# rPi.net
KiCad netlist of a schematic drawn in Altium Designer
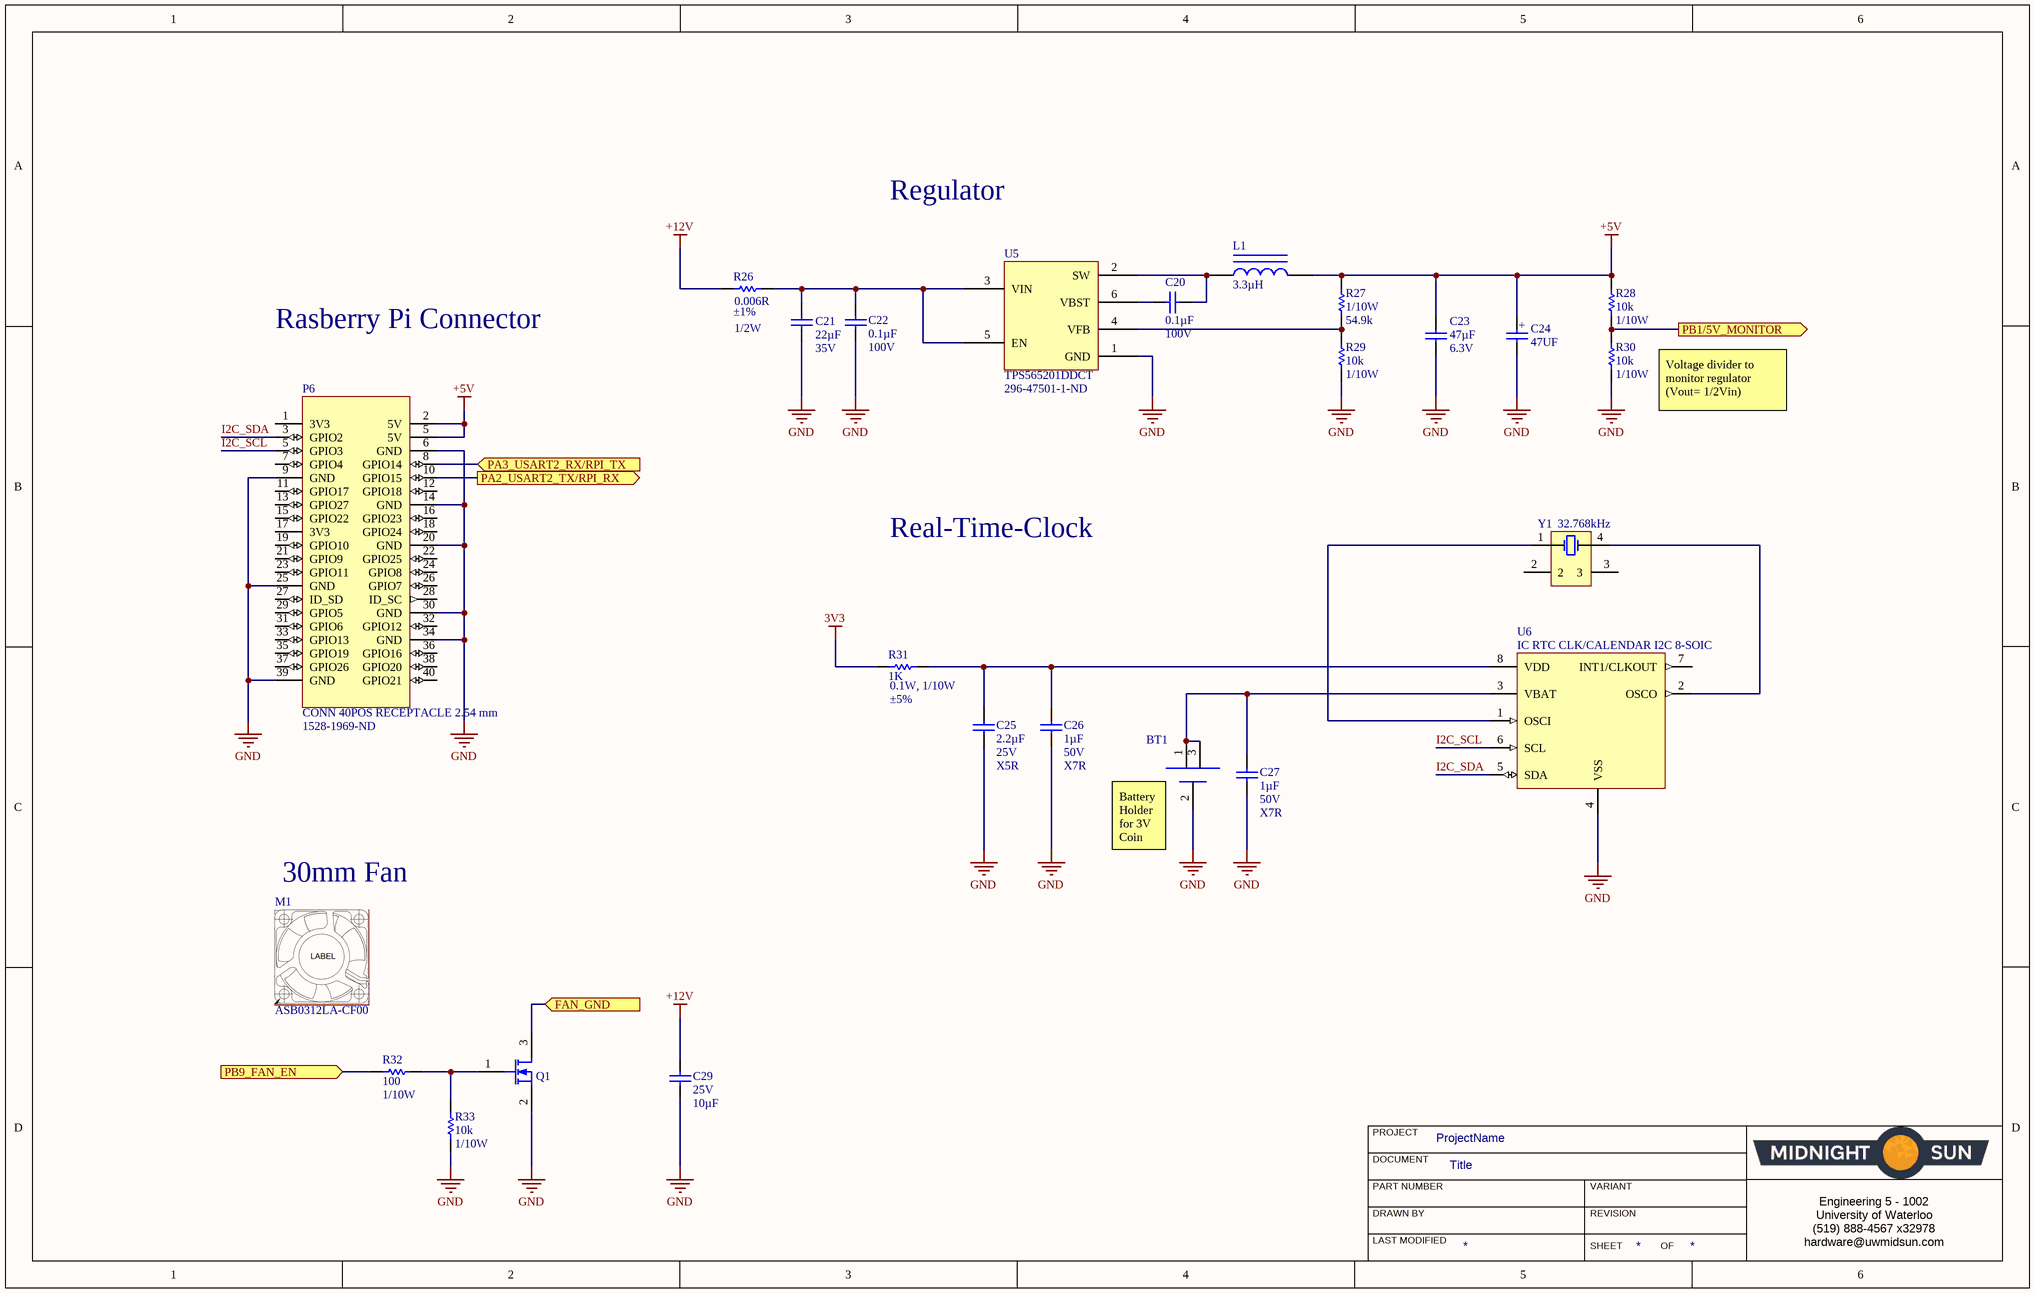
[diagram p0: rPi.SchDoc]

(export (version "E")
  (design (tool "Eeschema 10.0.6"))
  (components
    (comp (ref "BT1")
      (value "HOLDER BATTERY COIN 12MM DIA")
      (footprint "HOLDER COIN CELL 1220 3V")
      (description "Coin cell holder smd")
      (fields
        (field (name "MANUFACTURER") "Keystone Electronics")
        (field (name "MANUFACTURER PART NUMBER") "3000")
      )
      (libsource (lib "Schematic Diagrams") (part "HOLDER BATTERY COIN 12MM DIA"))
    )
    (comp (ref "C20")
      (value "CAP CER 0.1UF 100V 10% X7R 0805")
      (footprint "CAP, 0805")
      (description "0.1µF ±10% 100V Ceramic Capacitor X7R 0805 (2012 Metric)")
      (fields
        (field (name "TOLERANCE") "±10%")
        (field (name "CAPACITANCE") "0.1µF")
        (field (name "VOLTAGE") "100V")
      )
      (libsource (lib "Schematic Diagrams") (part "CAP CER 0.1UF 100V 10% X7R 0805"))
    )
    (comp (ref "C21")
      (value "CAP CER 22UF 35V X5R 0805")
      (footprint "CAP, 0805")
      (description "22µF ±20% 35V Ceramic Capacitor X5R 0805 (2012 Metric)")
      (fields
        (field (name "MANUFACTURER") "TDK")
        (field (name "MANUFACTURER PART NUMBER") "C2012X5R1V226M125AC")
      )
      (libsource (lib "Schematic Diagrams") (part "CAP CER 22UF 35V X5R 0805"))
    )
    (comp (ref "C22")
      (value "CAP CER 0.1UF 100V 10% X7R 0805")
      (footprint "CAP, 0805")
      (description "0.1µF ±10% 100V Ceramic Capacitor X7R 0805 (2012 Metric)")
      (fields
        (field (name "TOLERANCE") "±10%")
        (field (name "CAPACITANCE") "0.1µF")
        (field (name "VOLTAGE") "100V")
      )
      (libsource (lib "Schematic Diagrams") (part "CAP CER 0.1UF 100V 10% X7R 0805"))
    )
    (comp (ref "C23")
      (value "CAP CER 47UF 6.3V X7R 1210")
      (footprint "1210")
      (description "47µF ±10% 6.3V Ceramic Capacitor X7R 1210 (3225 Metric)")
      (fields
        (field (name "MANUFACTURER") "Murata")
        (field (name "MANUFACTURER PART NUMBER") "GCJ32ER70J476KE01L")
      )
      (libsource (lib "Schematic Diagrams") (part "CAP CER 47UF 6.3V X7R 1210"))
    )
    (comp (ref "C24")
      (value "47UF")
      (footprint "CAP ALUM 6.3MM RADIAL SMD")
      (description "47µF 35V Aluminum Electrolytic Capacitors Radial, Can - SMD 1000 Hrs @ 85°C")
      (fields
        (field (name "MANUFACTURER") "Panasonic")
        (field (name "MANUFACTURER PART NUMBER") "EEE-1VA470WP")
      )
      (libsource (lib "Schematic Diagrams") (part "CAP ALUM 47UF 20% 35V SMD"))
    )
    (comp (ref "C25")
      (value "CAP CER 2.2UF 25V 10% X5R 0603")
      (footprint "CAP, 0603")
      (description "2.2µF ±10% 25V Ceramic Capacitor X5R 0603 (1608 Metric)")
      (fields
        (field (name "TOLERANCE") "±10%")
        (field (name "CAPACITANCE") "2.2µF")
        (field (name "VOLTAGE") "25V")
        (field (name "TEMPERATURE COEFFICIENT") "X5R")
      )
      (libsource (lib "Schematic Diagrams") (part "CAP CER 2.2UF 25V 10% X5R 0603"))
    )
    (comp (ref "C26")
      (value "CAP CER 1UF 50V 10% X7R 0603")
      (footprint "CAP, 0603")
      (description "1µF ±10% 50V Ceramic Capacitor X7R 0603 (1608 Metric)")
      (fields
        (field (name "TOLERANCE") "±10%")
        (field (name "CAPACITANCE") "1µF")
        (field (name "VOLTAGE") "50V")
        (field (name "TEMPERATURE COEFFICIENT") "X7R")
      )
      (libsource (lib "Schematic Diagrams") (part "CAP CER 1UF 50V 10% X7R 0603"))
    )
    (comp (ref "C27")
      (value "CAP CER 1UF 50V 10% X7R 0603")
      (footprint "CAP, 0603")
      (description "1µF ±10% 50V Ceramic Capacitor X7R 0603 (1608 Metric)")
      (fields
        (field (name "TOLERANCE") "±10%")
        (field (name "CAPACITANCE") "1µF")
        (field (name "VOLTAGE") "50V")
        (field (name "TEMPERATURE COEFFICIENT") "X7R")
      )
      (libsource (lib "Schematic Diagrams") (part "CAP CER 1UF 50V 10% X7R 0603"))
    )
    (comp (ref "C29")
      (value "CAP CER 10uF 25V 10% X5R 0805")
      (footprint "CAP, 0805")
      (description "10µF ±10% 25V Ceramic Capacitor X5R 0805 (2012 Metric)")
      (fields
        (field (name "MANUFACTURER") "Murata Electronics North America")
        (field (name "MANUFACTURER PART NUMBER") "GRM21BR61E106KA73L")
        (field (name "VOLTAGE - RATED") "25V")
        (field (name "CAPACITANCE") "10µF")
      )
      (libsource (lib "altium-import") (part "root_0_CAP CER 10uF 25V 10% X5R 0805_"))
    )
    (comp (ref "L1")
      (value "IND 3.3uH 5.2A 20MOHM SMD")
      (footprint "IND 3.3UH 5.2A 20 MOHM SMD VLP8040")
      (description "3.3µH Shielded Wirewound Inductor 5.2A 20 mOhm Max Nonstandard")
      (fields
        (field (name "MANUFACTURER") "TDK Corporation")
        (field (name "MANUFACTURER PART NUMBER") "VLS201612CX-3R3M")
        (field (name "INDUCTANCE") "3.3µH")
      )
      (libsource (lib "Schematic Diagrams") (part "IND 3.3uH 5.2A 20MOHM SMD"))
    )
    (comp (ref "M1")
      (value "FAN AXIAL 30x10MM 12VDC")
      (footprint "FAN AXIAL 30x10MM 12VDC")
      (description "FAN AXIAL 30X10MM 12VDC WIRE")
      (fields
        (field (name "MANUFACTURER") "Delta Design")
        (field (name "MANUFACTURER PART NUMBER") "ASB0312LA-CF00")
      )
      (libsource (lib "altium-import") (part "root_0_FAN AXIAL 30x10MM 12VDC_"))
    )
    (comp (ref "P6")
      (value "CONN 40POS RECEPTACLE 2.54 mm")
      (footprint "CONN 40POS RECEPTACLE 2.54 MM")
      (description "GPIO HEADER FOR RASPBERRYPI A+/B")
      (fields
        (field (name "MANUFACTURER") "Adafruit Industries")
        (field (name "MANUFACTURER PART NUMBER") "1992")
        (field (name "SUPPLIER PART NUMBER 1") "1528-1969-ND")
      )
      (libsource (lib "Schematic Diagrams") (part "CONN 40POS RECEPTACLE 2.54 mm"))
    )
    (comp (ref "Q1")
      (value "MOSFET N-CH 30V 6.2A 0.9W SOT-23")
      (footprint "MOSFET N-CH 30V 6.2A 0.9W SOT-23")
      (description "N-Channel 30V 6.2A (Ta) 900mW (Ta) Surface Mount SOT-23")
      (fields (field (name "MANUFACTURER") "Diodes") (field (name "MANUFACTURER PART NUMBER") "DMN3023L-7"))
      (libsource (lib "altium-import") (part "root_0_MOSFET N-CH 30V 6.2A 0.9W SOT-23_"))
    )
    (comp (ref "R26")
      (value "RES 0.006 OHM 1% 1/2W 1206")
      (footprint "RES 1206")
      (fields
        (field (name "TOLERANCE") "±1%")
        (field (name "MANUFACTURER") "Panasonic Electronic Components")
        (field (name "MANUFACTURER PART NUMBER") "ERJ-MP2KF6M0U")
        (field (name "RESISTANCE (OHMS)") "0.006R")
        (field (name "POWER (WATTS)") "1/2W")
      )
      (libsource (lib "Schematic Diagrams") (part "RES 0.006 OHM 1% 1/2W 1206"))
    )
    (comp (ref "R27")
      (value "RES 54.9K OHM 1% 1/10W 0603")
      (footprint "RES, 0603")
      (description "54.9k Ohm ±1% 0.1W, 1/10W Chip Resistor 0603 (1608 Metric) Automotive AEC-Q200 Thick Film")
      (fields
        (field (name "MANUFACTURER") "Panasonic Electronic Components")
        (field (name "MANUFACTURER PART NUMBER") "ERJ-3EKF5492V")
        (field (name "POWER (WATTS)") "1/10W")
        (field (name "RESISTANCE (OHMS)") "54.9k")
      )
      (libsource (lib "Schematic Diagrams") (part "RES 54.9K OHM 1% 1/10W 0603"))
    )
    (comp (ref "R28")
      (value "RES 10K OHM 1% 1/10W 0603")
      (footprint "RES, 0603")
      (description "RES SMD 10K OHM 1% 1/10W 0603")
      (fields
        (field (name "TOLERANCE") "±1%")
        (field (name "RESISTANCE") "10k")
        (field (name "POWER") "1/10W")
      )
      (libsource (lib "Schematic Diagrams") (part "RES 10K OHM 1% 1/10W 0603"))
    )
    (comp (ref "R29")
      (value "RES 10K OHM 1% 1/10W 0603")
      (footprint "RES, 0603")
      (description "RES SMD 10K OHM 1% 1/10W 0603")
      (fields
        (field (name "TOLERANCE") "±1%")
        (field (name "RESISTANCE") "10k")
        (field (name "POWER") "1/10W")
      )
      (libsource (lib "Schematic Diagrams") (part "RES 10K OHM 1% 1/10W 0603"))
    )
    (comp (ref "R30")
      (value "RES 10K OHM 1% 1/10W 0603")
      (footprint "RES, 0603")
      (description "RES SMD 10K OHM 1% 1/10W 0603")
      (fields
        (field (name "TOLERANCE") "±1%")
        (field (name "RESISTANCE") "10k")
        (field (name "POWER") "1/10W")
      )
      (libsource (lib "Schematic Diagrams") (part "RES 10K OHM 1% 1/10W 0603"))
    )
    (comp (ref "R31")
      (value "1K")
      (footprint "RES, 0603")
      (description "1k Ohm ±5% 0.1W, 1/10W Chip Resistor 0603 (1608 Metric)")
      (fields
        (field (name "MANUFACTURER") "Yageo")
        (field (name "MANUFACTURER PART NUMBER") "RC0603JR-071KL")
        (field (name "TOLERANCE") "±5%")
        (field (name "POWER (WATTS)") "0.1W, 1/10W")
      )
      (libsource (lib "Schematic Diagrams") (part "RES 1K OHM 5% 1/10W 0603"))
    )
    (comp (ref "R32")
      (value "RES 100 OHM 1% 1/10W 0603")
      (footprint "RES, 0603")
      (description "100 Ohm ±1% 0.1W, 1/10W Chip Resistor 0603 (1608 Metric) Moisture Resistant Thick Film")
      (fields
        (field (name "TOLERANCE") "±1%")
        (field (name "RESISTANCE") "100")
        (field (name "POWER") "1/10W")
      )
      (libsource (lib "altium-import") (part "root_1_RES 100 OHM 1% 1/10W 0603_"))
    )
    (comp (ref "R33")
      (value "RES 10K OHM 1% 1/10W 0603")
      (footprint "RES, 0603")
      (description "RES SMD 10K OHM 1% 1/10W 0603")
      (fields
        (field (name "TOLERANCE") "±1%")
        (field (name "RESISTANCE") "10k")
        (field (name "POWER") "1/10W")
      )
      (libsource (lib "altium-import") (part "root_0_RES 10K OHM 1% 1/10W 0603_"))
    )
    (comp (ref "U5")
      (value "IC REG BUCK 4.5V TO 17V, 5A, SYNCHRONOUS STE")
      (footprint "IC REG BUCK 4.5V TO 17V, 5A")
      (description "Buck Switching Regulator IC Positive Adjustable 0.6V 1 Output 5A SOT-23-6 Thin, TSOT-23-6")
      (fields
        (field (name "MANUFACTURER") "Texas Instruments")
        (field (name "MANUFACTURER PART NUMBER") "TPS565201DDCT")
        (field (name "SUPPLIER PART NUMBER 1") "296-47501-1-ND")
      )
      (libsource (lib "Schematic Diagrams") (part "IC REG BUCK 4.5V TO 17V, 5A, SYNCHRONOUS STE"))
    )
    (comp (ref "U6")
      (value "IC RTC CLK/CALENDAR I2C 8-SOIC")
      (footprint "SOIC8")
      (description "Real Time Clock (RTC) IC Clock/Calendar I²C, 2-Wire Serial 8-SOIC (0.154\", 3.90mm Width)")
      (fields
        (field (name "MANUFACTURER") "NXP Semiconductors")
        (field (name "MANUFACTURER PART NUMBER") "PCF8523T/1,118")
      )
      (libsource (lib "Schematic Diagrams") (part "IC RTC CLK/CALENDAR I2C 8-SOIC"))
    )
    (comp (ref "Y1")
      (value "CRYSTAL 32.7680KHZ 12.5PF SMD")
      (footprint "4-SOJ")
      (description "32.768kHz ±20ppm Crystal 12.5pF 50 kOhms 4-SOJ, 5.50mm pitch")
      (fields
        (field (name "MANUFACTURER") "ECS International")
        (field (name "MANUFACTURER PART NUMBER") "ECS-.327-12.5-17X-TR")
        (field (name "FREQUENCY") "32.768kHz")
      )
      (libsource (lib "Schematic Diagrams") (part "CRYSTAL 32.7680KHZ 12.5PF SMD"))
    )
  )
  (nets
    (net (code "1") (name "+5V") (class "Default")
      (node (ref "C23") (pin "1") (pinfunction "1_1") (pintype "passive"))
      (node (ref "C24") (pin "1") (pinfunction "1_1") (pintype "passive"))
      (node (ref "L1") (pin "2") (pinfunction "2_2") (pintype "passive"))
      (node (ref "P6") (pin "2") (pinfunction "5V_2") (pintype "power_in"))
      (node (ref "P6") (pin "5") (pinfunction "5V_5") (pintype "power_in"))
      (node (ref "R27") (pin "1") (pinfunction "1_1") (pintype "passive"))
      (node (ref "R28") (pin "1") (pinfunction "1_1") (pintype "passive"))
    )
    (net (code "2") (name "+12V") (class "Default")
      (node (ref "C29") (pin "1") (pinfunction "1_1") (pintype "passive"))
      (node (ref "R26") (pin "1") (pinfunction "1_1") (pintype "passive"))
    )
    (net (code "3") (name "/FAN_GND") (class "Default")
      (node (ref "Q1") (pin "3") (pinfunction "D_3") (pintype "passive"))
    )
    (net (code "4") (name "/I2C_SCL") (class "Default")
      (node (ref "P6") (pin "5") (pinfunction "GPIO3_5") (pintype "bidirectional"))
      (node (ref "U6") (pin "6") (pinfunction "SCL_6") (pintype "input"))
    )
    (net (code "5") (name "/I2C_SDA") (class "Default")
      (node (ref "P6") (pin "3") (pinfunction "GPIO2_3") (pintype "bidirectional"))
      (node (ref "U6") (pin "5") (pinfunction "SDA_5") (pintype "bidirectional"))
    )
    (net (code "6") (name "/PA2_USART2_TX{slash}RPI_RX") (class "Default")
      (node (ref "P6") (pin "10") (pinfunction "GPIO15_10") (pintype "bidirectional"))
    )
    (net (code "7") (name "/PA3_USART2_RX{slash}RPI_TX") (class "Default")
      (node (ref "P6") (pin "8") (pinfunction "GPIO14_8") (pintype "bidirectional"))
    )
    (net (code "8") (name "/PB1{slash}5V_MONITOR") (class "Default")
      (node (ref "R28") (pin "2") (pinfunction "2_2") (pintype "passive"))
      (node (ref "R30") (pin "1") (pinfunction "1_1") (pintype "passive"))
    )
    (net (code "9") (name "/PB9_FAN_EN") (class "Default")
      (node (ref "R32") (pin "1") (pinfunction "1_1") (pintype "passive"))
    )
    (net (code "10") (name "3V3") (class "Default")
      (node (ref "R31") (pin "1") (pinfunction "1_1") (pintype "passive"))
    )
    (net (code "11") (name "GND") (class "Default")
      (node (ref "BT1") (pin "2") (pinfunction "negative_2") (pintype "power_in"))
      (node (ref "C21") (pin "2") (pinfunction "2_2") (pintype "passive"))
      (node (ref "C22") (pin "2") (pinfunction "2_2") (pintype "passive"))
      (node (ref "C23") (pin "2") (pinfunction "2_2") (pintype "passive"))
      (node (ref "C24") (pin "2") (pinfunction "2_2") (pintype "passive"))
      (node (ref "C25") (pin "2") (pinfunction "2_2") (pintype "passive"))
      (node (ref "C26") (pin "2") (pinfunction "2_2") (pintype "passive"))
      (node (ref "C27") (pin "2") (pinfunction "2_2") (pintype "passive"))
      (node (ref "C29") (pin "2") (pinfunction "2_2") (pintype "passive"))
      (node (ref "P6") (pin "14") (pinfunction "GND_14") (pintype "power_in"))
      (node (ref "P6") (pin "20") (pinfunction "GND_20") (pintype "power_in"))
      (node (ref "P6") (pin "25") (pinfunction "GND_25") (pintype "power_in"))
      (node (ref "P6") (pin "30") (pinfunction "GND_30") (pintype "power_in"))
      (node (ref "P6") (pin "34") (pinfunction "GND_34") (pintype "power_in"))
      (node (ref "P6") (pin "39") (pinfunction "GND_39") (pintype "power_in"))
      (node (ref "P6") (pin "6") (pinfunction "GND_6") (pintype "power_in"))
      (node (ref "P6") (pin "9") (pinfunction "GND_9") (pintype "power_in"))
      (node (ref "Q1") (pin "2") (pinfunction "S_2") (pintype "passive"))
      (node (ref "R29") (pin "2") (pinfunction "2_2") (pintype "passive"))
      (node (ref "R30") (pin "2") (pinfunction "2_2") (pintype "passive"))
      (node (ref "R33") (pin "2") (pinfunction "2_2") (pintype "passive"))
      (node (ref "U5") (pin "1") (pinfunction "GND_1") (pintype "passive"))
      (node (ref "U6") (pin "4") (pinfunction "VSS_4") (pintype "passive"))
    )
    (net (code "12") (name "Net-(BT1-positive_1)") (class "Default")
      (node (ref "BT1") (pin "1") (pinfunction "positive_1_1") (pintype "power_in"))
      (node (ref "BT1") (pin "3") (pinfunction "positive_2_3") (pintype "power_in"))
      (node (ref "C27") (pin "1") (pinfunction "1_1") (pintype "passive"))
      (node (ref "U6") (pin "3") (pinfunction "VBAT_3") (pintype "power_in"))
    )
    (net (code "13") (name "Net-(Q1-G)") (class "Default")
      (node (ref "Q1") (pin "1") (pinfunction "G_1") (pintype "passive"))
      (node (ref "R32") (pin "2") (pinfunction "2_2") (pintype "passive"))
      (node (ref "R33") (pin "1") (pinfunction "1_1") (pintype "passive"))
    )
    (net (code "14") (name "Net-(U5-EN)") (class "Default")
      (node (ref "C21") (pin "1") (pinfunction "1_1") (pintype "passive"))
      (node (ref "C22") (pin "1") (pinfunction "1_1") (pintype "passive"))
      (node (ref "R26") (pin "2") (pinfunction "2_2") (pintype "passive"))
      (node (ref "U5") (pin "3") (pinfunction "VIN_3") (pintype "passive"))
      (node (ref "U5") (pin "5") (pinfunction "EN_5") (pintype "passive"))
    )
    (net (code "15") (name "Net-(U5-SW)") (class "Default")
      (node (ref "C20") (pin "2") (pinfunction "2_2") (pintype "passive"))
      (node (ref "L1") (pin "1") (pinfunction "1_1") (pintype "passive"))
      (node (ref "U5") (pin "2") (pinfunction "SW_2") (pintype "passive"))
    )
    (net (code "16") (name "Net-(U5-VBST)") (class "Default")
      (node (ref "C20") (pin "1") (pinfunction "1_1") (pintype "passive"))
      (node (ref "U5") (pin "6") (pinfunction "VBST_6") (pintype "passive"))
    )
    (net (code "17") (name "Net-(U5-VFB)") (class "Default")
      (node (ref "R27") (pin "2") (pinfunction "2_2") (pintype "passive"))
      (node (ref "R29") (pin "1") (pinfunction "1_1") (pintype "passive"))
      (node (ref "U5") (pin "4") (pinfunction "VFB_4") (pintype "passive"))
    )
    (net (code "18") (name "Net-(U6-OSCI)") (class "Default")
      (node (ref "U6") (pin "1") (pinfunction "OSCI_1") (pintype "input"))
      (node (ref "Y1") (pin "1") (pinfunction "1_1") (pintype "passive"))
    )
    (net (code "19") (name "Net-(U6-OSCO)") (class "Default")
      (node (ref "U6") (pin "2") (pinfunction "OSCO_2") (pintype "output"))
      (node (ref "Y1") (pin "4") (pinfunction "4_4") (pintype "passive"))
    )
    (net (code "20") (name "Net-(U6-VDD)") (class "Default")
      (node (ref "C25") (pin "1") (pinfunction "1_1") (pintype "passive"))
      (node (ref "C26") (pin "1") (pinfunction "1_1") (pintype "passive"))
      (node (ref "R31") (pin "2") (pinfunction "2_2") (pintype "passive"))
      (node (ref "U6") (pin "8") (pinfunction "VDD_8") (pintype "power_in"))
    )
    (net (code "21") (name "unconnected-(P6-3V3-Pad1)") (class "Default")
      (node (ref "P6") (pin "1") (pinfunction "3V3_1") (pintype "power_in"))
    )
    (net (code "22") (name "unconnected-(P6-3V3-Pad17)") (class "Default")
      (node (ref "P6") (pin "17") (pinfunction "3V3_17") (pintype "power_in"))
    )
    (net (code "23") (name "unconnected-(P6-GPIO4-Pad7)") (class "Default")
      (node (ref "P6") (pin "7") (pinfunction "GPIO4_7") (pintype "bidirectional"))
    )
    (net (code "24") (name "unconnected-(P6-GPIO5-Pad29)") (class "Default")
      (node (ref "P6") (pin "29") (pinfunction "GPIO5_29") (pintype "bidirectional"))
    )
    (net (code "25") (name "unconnected-(P6-GPIO6-Pad31)") (class "Default")
      (node (ref "P6") (pin "31") (pinfunction "GPIO6_31") (pintype "bidirectional"))
    )
    (net (code "26") (name "unconnected-(P6-GPIO7-Pad26)") (class "Default")
      (node (ref "P6") (pin "26") (pinfunction "GPIO7_26") (pintype "bidirectional"))
    )
    (net (code "27") (name "unconnected-(P6-GPIO8-Pad24)") (class "Default")
      (node (ref "P6") (pin "24") (pinfunction "GPIO8_24") (pintype "bidirectional"))
    )
    (net (code "28") (name "unconnected-(P6-GPIO9-Pad21)") (class "Default")
      (node (ref "P6") (pin "21") (pinfunction "GPIO9_21") (pintype "bidirectional"))
    )
    (net (code "29") (name "unconnected-(P6-GPIO10-Pad19)") (class "Default")
      (node (ref "P6") (pin "19") (pinfunction "GPIO10_19") (pintype "bidirectional"))
    )
    (net (code "30") (name "unconnected-(P6-GPIO11-Pad23)") (class "Default")
      (node (ref "P6") (pin "23") (pinfunction "GPIO11_23") (pintype "bidirectional"))
    )
    (net (code "31") (name "unconnected-(P6-GPIO12-Pad32)") (class "Default")
      (node (ref "P6") (pin "32") (pinfunction "GPIO12_32") (pintype "bidirectional"))
    )
    (net (code "32") (name "unconnected-(P6-GPIO13-Pad33)") (class "Default")
      (node (ref "P6") (pin "33") (pinfunction "GPIO13_33") (pintype "bidirectional"))
    )
    (net (code "33") (name "unconnected-(P6-GPIO16-Pad36)") (class "Default")
      (node (ref "P6") (pin "36") (pinfunction "GPIO16_36") (pintype "bidirectional"))
    )
    (net (code "34") (name "unconnected-(P6-GPIO17-Pad11)") (class "Default")
      (node (ref "P6") (pin "11") (pinfunction "GPIO17_11") (pintype "bidirectional"))
    )
    (net (code "35") (name "unconnected-(P6-GPIO18-Pad12)") (class "Default")
      (node (ref "P6") (pin "12") (pinfunction "GPIO18_12") (pintype "bidirectional"))
    )
    (net (code "36") (name "unconnected-(P6-GPIO19-Pad35)") (class "Default")
      (node (ref "P6") (pin "35") (pinfunction "GPIO19_35") (pintype "bidirectional"))
    )
    (net (code "37") (name "unconnected-(P6-GPIO20-Pad38)") (class "Default")
      (node (ref "P6") (pin "38") (pinfunction "GPIO20_38") (pintype "bidirectional"))
    )
    (net (code "38") (name "unconnected-(P6-GPIO21-Pad40)") (class "Default")
      (node (ref "P6") (pin "40") (pinfunction "GPIO21_40") (pintype "bidirectional"))
    )
    (net (code "39") (name "unconnected-(P6-GPIO22-Pad15)") (class "Default")
      (node (ref "P6") (pin "15") (pinfunction "GPIO22_15") (pintype "bidirectional"))
    )
    (net (code "40") (name "unconnected-(P6-GPIO23-Pad16)") (class "Default")
      (node (ref "P6") (pin "16") (pinfunction "GPIO23_16") (pintype "bidirectional"))
    )
    (net (code "41") (name "unconnected-(P6-GPIO24-Pad18)") (class "Default")
      (node (ref "P6") (pin "18") (pinfunction "GPIO24_18") (pintype "bidirectional"))
    )
    (net (code "42") (name "unconnected-(P6-GPIO25-Pad22)") (class "Default")
      (node (ref "P6") (pin "22") (pinfunction "GPIO25_22") (pintype "bidirectional"))
    )
    (net (code "43") (name "unconnected-(P6-GPIO26-Pad37)") (class "Default")
      (node (ref "P6") (pin "37") (pinfunction "GPIO26_37") (pintype "bidirectional"))
    )
    (net (code "44") (name "unconnected-(P6-GPIO27-Pad13)") (class "Default")
      (node (ref "P6") (pin "13") (pinfunction "GPIO27_13") (pintype "bidirectional"))
    )
    (net (code "45") (name "unconnected-(P6-ID_SC-Pad28)") (class "Default")
      (node (ref "P6") (pin "28") (pinfunction "ID_SC_28") (pintype "output"))
    )
    (net (code "46") (name "unconnected-(P6-ID_SD-Pad27)") (class "Default")
      (node (ref "P6") (pin "27") (pinfunction "ID_SD_27") (pintype "bidirectional"))
    )
    (net (code "47") (name "unconnected-(U6-INT1{slash}CLKOUT-Pad7)") (class "Default")
      (node (ref "U6") (pin "7") (pinfunction "INT1/CLKOUT_7") (pintype "output"))
    )
    (net (code "48") (name "unconnected-(Y1-Pad2)") (class "Default")
      (node (ref "Y1") (pin "2") (pinfunction "2_2") (pintype "passive"))
    )
    (net (code "49") (name "unconnected-(Y1-Pad3)") (class "Default")
      (node (ref "Y1") (pin "3") (pinfunction "3_3") (pintype "passive"))
    )
  )
)
